# XIAO_ESP32C3.net
KiCad netlist of a schematic drawn in EAGLE
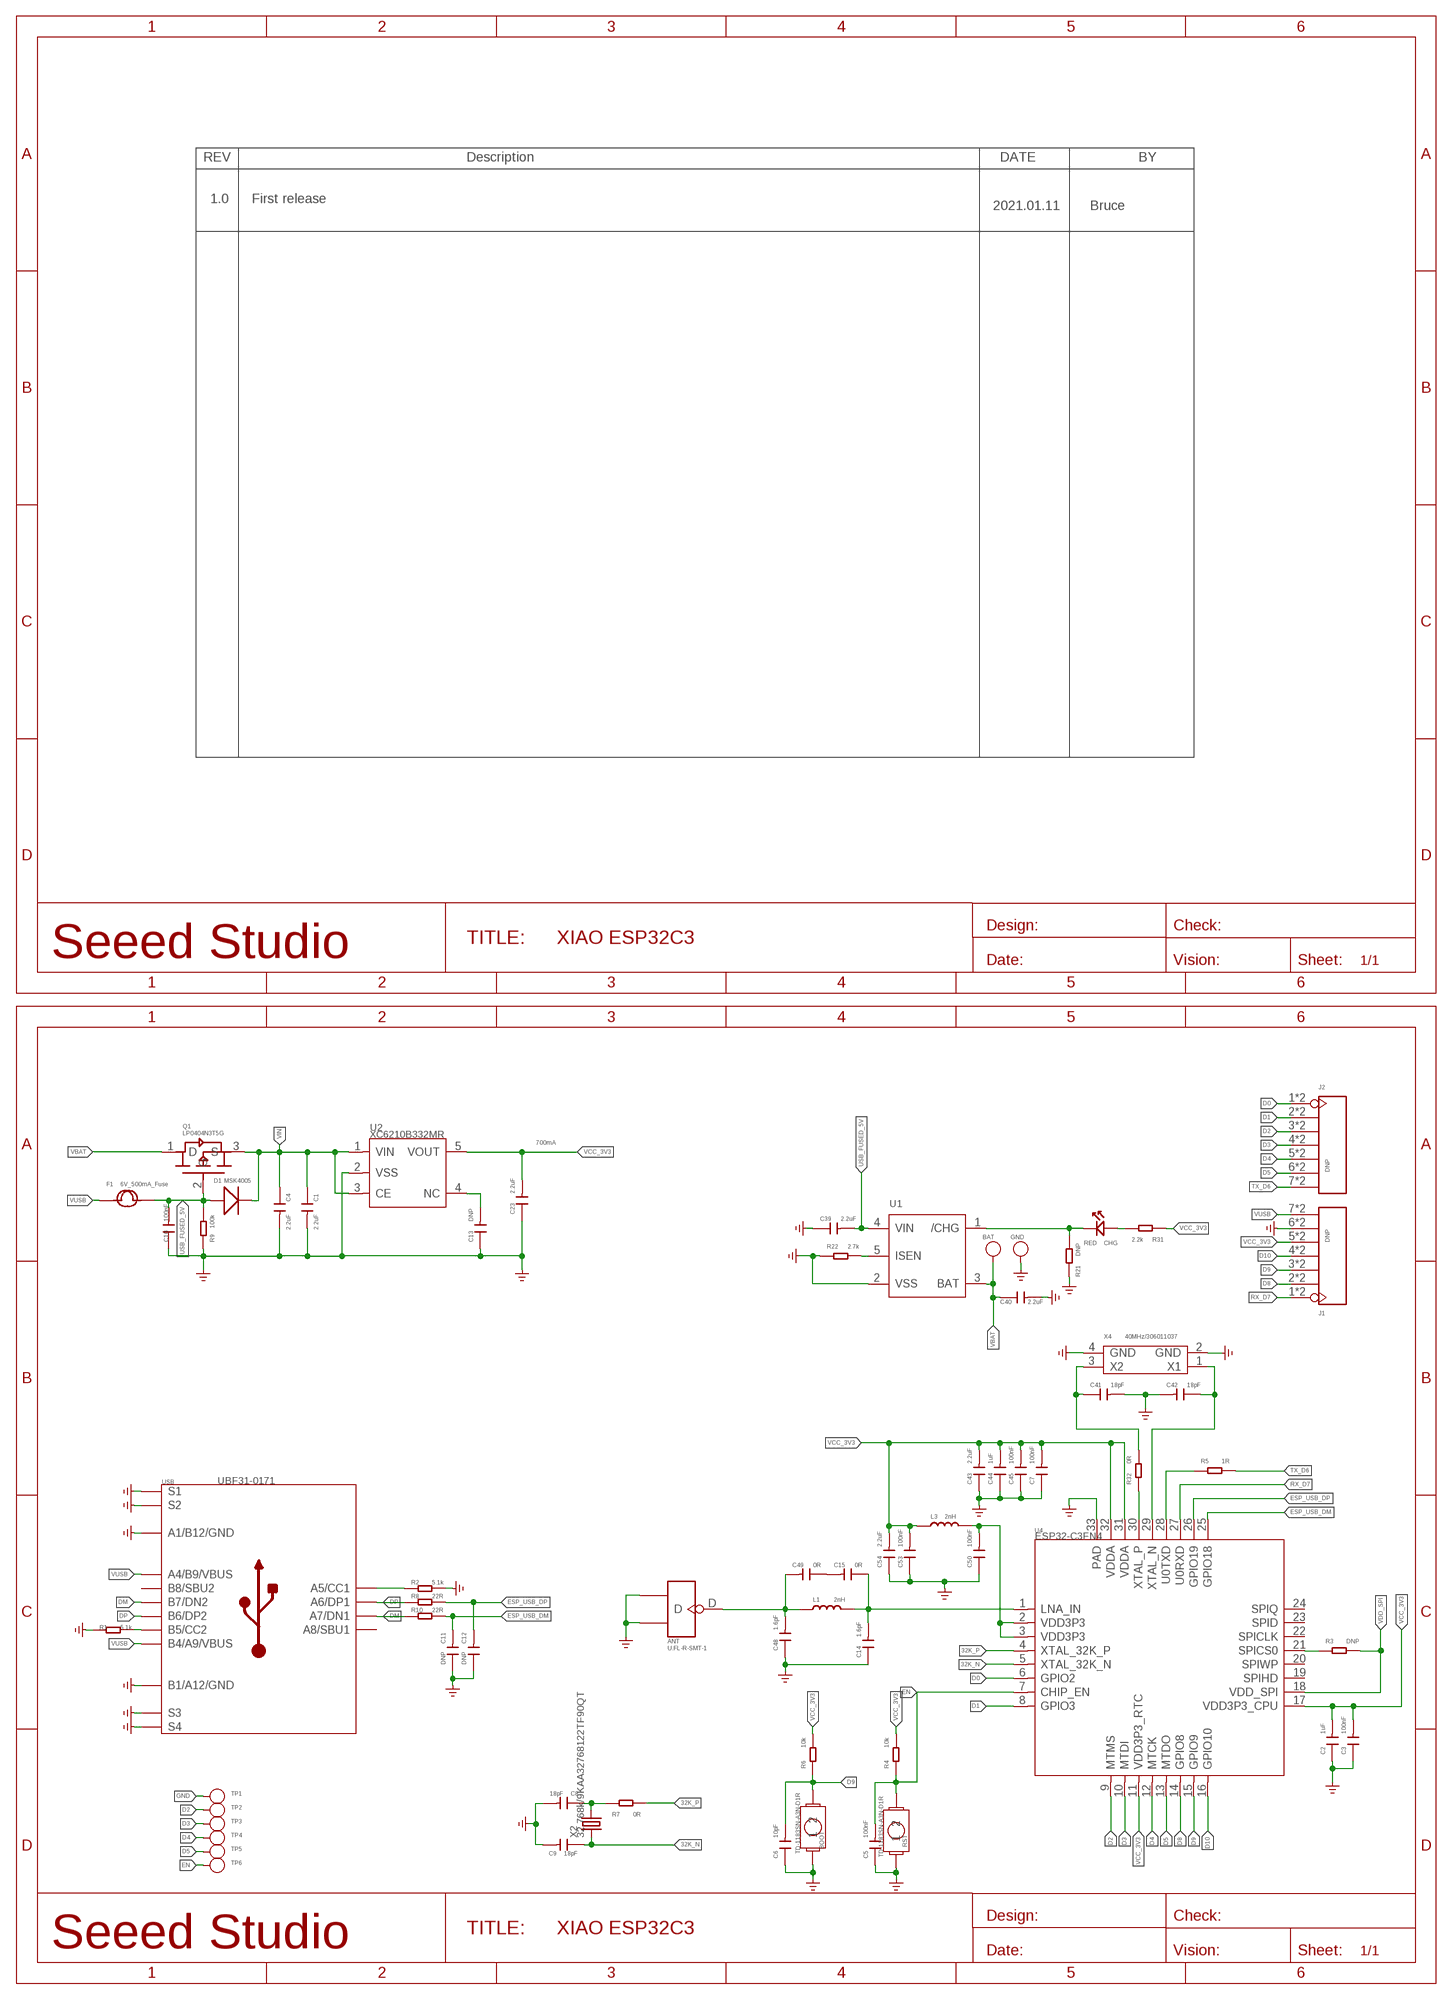
[diagram p0: schematic, sheet 1]

(export (version "E")
  (design (tool "Eeschema 10.0.6"))
  (components
    (comp (ref "ANT")
      (value "U.FL-R-SMT-1")
      (footprint "eagle-import:U-FL3P-SMD-2.6X2.6X1.0MM")
      (libsource (lib "eagle-import") (part "ANTENNA-U-FL-320110048"))
    )
    (comp (ref "BAT")
      (value "DNP")
      (footprint "eagle-import:TP-80X40MIL")
      (libsource (lib "eagle-import") (part "TEST-POINT'4080'"))
    )
    (comp (ref "BOOT")
      (value "TD-1183SN-A3N-D1R")
      (footprint "eagle-import:BUTTON_TD1183SA")
      (libsource (lib "eagle-import") (part "BUTTON_TD1183SA"))
    )
    (comp (ref "C1")
      (value "2.2uF")
      (footprint "eagle-import:C0201")
      (libsource (lib "eagle-import") (part "CAP-0201"))
    )
    (comp (ref "C2")
      (value "1uF")
      (footprint "eagle-import:C0201")
      (libsource (lib "eagle-import") (part "CAP-0201"))
    )
    (comp (ref "C3")
      (value "100nF")
      (footprint "eagle-import:C0201")
      (libsource (lib "eagle-import") (part "CAP-0201"))
    )
    (comp (ref "C4")
      (value "2.2uF")
      (footprint "eagle-import:C0201")
      (libsource (lib "eagle-import") (part "CAP-0201"))
    )
    (comp (ref "C5")
      (value "100nF")
      (footprint "eagle-import:C0201")
      (libsource (lib "eagle-import") (part "CAP-0201"))
    )
    (comp (ref "C6")
      (value "10pF")
      (footprint "eagle-import:C0201")
      (libsource (lib "eagle-import") (part "CAP-0201"))
    )
    (comp (ref "C7")
      (value "100nF")
      (footprint "eagle-import:C0201")
      (libsource (lib "eagle-import") (part "CAP-0201"))
    )
    (comp (ref "C8")
      (value "18pF")
      (footprint "eagle-import:C0201")
      (libsource (lib "eagle-import") (part "CAP-0201"))
    )
    (comp (ref "C9")
      (value "18pF")
      (footprint "eagle-import:C0201")
      (libsource (lib "eagle-import") (part "CAP-0201"))
    )
    (comp (ref "C10")
      (value "100nF")
      (footprint "eagle-import:C0201")
      (libsource (lib "eagle-import") (part "CAP-0201"))
    )
    (comp (ref "C11")
      (value "DNP")
      (footprint "eagle-import:C0201")
      (libsource (lib "eagle-import") (part "CAP-0201"))
    )
    (comp (ref "C12")
      (value "DNP")
      (footprint "eagle-import:C0201")
      (libsource (lib "eagle-import") (part "CAP-0201"))
    )
    (comp (ref "C13")
      (value "DNP")
      (footprint "eagle-import:C0201")
      (libsource (lib "eagle-import") (part "CAP-0201"))
    )
    (comp (ref "C14")
      (value "1.6pF")
      (footprint "eagle-import:C0201")
      (libsource (lib "eagle-import") (part "CAP-0201"))
    )
    (comp (ref "C15")
      (value "0R")
      (footprint "eagle-import:C0201")
      (libsource (lib "eagle-import") (part "CAP-0201"))
    )
    (comp (ref "C23")
      (value "2.2uF")
      (footprint "eagle-import:C0201")
      (libsource (lib "eagle-import") (part "CAP-0201"))
    )
    (comp (ref "C39")
      (value "2.2uF")
      (footprint "eagle-import:C0201")
      (libsource (lib "eagle-import") (part "CAP-0201"))
    )
    (comp (ref "C40")
      (value "2.2uF")
      (footprint "eagle-import:C0201")
      (libsource (lib "eagle-import") (part "CAP-0201"))
    )
    (comp (ref "C41")
      (value "18pF")
      (footprint "eagle-import:C0201")
      (libsource (lib "eagle-import") (part "CAP-0201"))
    )
    (comp (ref "C42")
      (value "18pF")
      (footprint "eagle-import:C0201")
      (libsource (lib "eagle-import") (part "CAP-0201"))
    )
    (comp (ref "C43")
      (value "2.2uF")
      (footprint "eagle-import:C0201")
      (libsource (lib "eagle-import") (part "CAP-0201"))
    )
    (comp (ref "C44")
      (value "1uF")
      (footprint "eagle-import:C0201")
      (libsource (lib "eagle-import") (part "CAP-0201"))
    )
    (comp (ref "C45")
      (value "100nF")
      (footprint "eagle-import:C0201")
      (libsource (lib "eagle-import") (part "CAP-0201"))
    )
    (comp (ref "C48")
      (value "1.6pF")
      (footprint "eagle-import:C0201")
      (libsource (lib "eagle-import") (part "CAP-0201"))
    )
    (comp (ref "C49")
      (value "0R")
      (footprint "eagle-import:C0201")
      (libsource (lib "eagle-import") (part "CAP-0201"))
    )
    (comp (ref "C50")
      (value "100nF")
      (footprint "eagle-import:C0201")
      (libsource (lib "eagle-import") (part "CAP-0201"))
    )
    (comp (ref "C53")
      (value "100nF")
      (footprint "eagle-import:C0201")
      (libsource (lib "eagle-import") (part "CAP-0201"))
    )
    (comp (ref "C54")
      (value "2.2uF")
      (footprint "eagle-import:C0201")
      (libsource (lib "eagle-import") (part "CAP-0201"))
    )
    (comp (ref "CHG")
      (value "RED")
      (footprint "eagle-import:LED-0402")
      (libsource (lib "eagle-import") (part "LED-0402"))
    )
    (comp (ref "D1")
      (value "MSK4005")
      (footprint "eagle-import:SOD-523")
      (libsource (lib "eagle-import") (part "DIODE'0603'"))
    )
    (comp (ref "F1")
      (value "6V_500mA_Fuse")
      (footprint "eagle-import:F0603")
      (libsource (lib "eagle-import") (part "FUSE0603"))
    )
    (comp (ref "GND")
      (value "DNP")
      (footprint "eagle-import:TP-80X40MIL")
      (libsource (lib "eagle-import") (part "TEST-POINT'4080'"))
    )
    (comp (ref "J1")
      (value "DNP")
      (footprint "eagle-import:H7-HALF-HOLE-2.54")
      (libsource (lib "eagle-import") (part "HEADER-7P-HALF-HOLE-2.54"))
    )
    (comp (ref "J2")
      (value "DNP")
      (footprint "eagle-import:H7-HALF-HOLE-2.54")
      (libsource (lib "eagle-import") (part "HEADER-7P-HALF-HOLE-2.54"))
    )
    (comp (ref "L1")
      (value "2nH")
      (footprint "eagle-import:L0201")
      (libsource (lib "eagle-import") (part "INDUCTOR-0201"))
    )
    (comp (ref "L3")
      (value "2nH")
      (footprint "eagle-import:L0201")
      (libsource (lib "eagle-import") (part "INDUCTOR-0201"))
    )
    (comp (ref "Q1")
      (value "LP0404N3T5G")
      (footprint "eagle-import:PMOS_1.0_0.6_0.35MM")
      (libsource (lib "eagle-import") (part "PMOS_1.00.60.35MM"))
    )
    (comp (ref "R1")
      (value "5.1k")
      (footprint "eagle-import:R0201")
      (libsource (lib "eagle-import") (part "RES-0201"))
    )
    (comp (ref "R2")
      (value "5.1k")
      (footprint "eagle-import:R0201")
      (libsource (lib "eagle-import") (part "RES-0201"))
    )
    (comp (ref "R3")
      (value "DNP")
      (footprint "eagle-import:R0201")
      (libsource (lib "eagle-import") (part "RES-0201"))
    )
    (comp (ref "R4")
      (value "10k")
      (footprint "eagle-import:R0201")
      (libsource (lib "eagle-import") (part "RES-0201"))
    )
    (comp (ref "R5")
      (value "1R")
      (footprint "eagle-import:R0201")
      (libsource (lib "eagle-import") (part "RES-0201"))
    )
    (comp (ref "R6")
      (value "10k")
      (footprint "eagle-import:R0201")
      (libsource (lib "eagle-import") (part "RES-0201"))
    )
    (comp (ref "R7")
      (value "0R")
      (footprint "eagle-import:R0201")
      (libsource (lib "eagle-import") (part "RES-0201"))
    )
    (comp (ref "R8")
      (value "22R")
      (footprint "eagle-import:R0201")
      (libsource (lib "eagle-import") (part "RES-0201"))
    )
    (comp (ref "R9")
      (value "100k")
      (footprint "eagle-import:R0201")
      (libsource (lib "eagle-import") (part "RES-0201"))
    )
    (comp (ref "R10")
      (value "22R")
      (footprint "eagle-import:R0201")
      (libsource (lib "eagle-import") (part "RES-0201"))
    )
    (comp (ref "R21")
      (value "DNP")
      (footprint "eagle-import:R0201")
      (libsource (lib "eagle-import") (part "R-0201"))
    )
    (comp (ref "R22")
      (value "2.7k")
      (footprint "eagle-import:R0201")
      (libsource (lib "eagle-import") (part "RES-0201"))
    )
    (comp (ref "R31")
      (value "2.2k")
      (footprint "eagle-import:R0201")
      (libsource (lib "eagle-import") (part "RES-0201"))
    )
    (comp (ref "R32")
      (value "0R")
      (footprint "eagle-import:R0201")
      (libsource (lib "eagle-import") (part "RES-0201"))
    )
    (comp (ref "RST")
      (value "TD-1183SN-A3N-D1R")
      (footprint "eagle-import:BUTTON_TD1183SA")
      (libsource (lib "eagle-import") (part "BUTTON_TD1183SA"))
    )
    (comp (ref "TP1")
      (value "DNP")
      (footprint "eagle-import:TP-D45MIL")
      (libsource (lib "eagle-import") (part "TEST-POINT'4545'"))
    )
    (comp (ref "TP2")
      (value "DNP")
      (footprint "eagle-import:TP-D45MIL")
      (libsource (lib "eagle-import") (part "TEST-POINT'4545'"))
    )
    (comp (ref "TP3")
      (value "DNP")
      (footprint "eagle-import:TP-D45MIL")
      (libsource (lib "eagle-import") (part "TEST-POINT'4545'"))
    )
    (comp (ref "TP4")
      (value "DNP")
      (footprint "eagle-import:TP-D45MIL")
      (libsource (lib "eagle-import") (part "TEST-POINT'4545'"))
    )
    (comp (ref "TP5")
      (value "DNP")
      (footprint "eagle-import:TP-D45MIL")
      (libsource (lib "eagle-import") (part "TEST-POINT'4545'"))
    )
    (comp (ref "TP6")
      (value "DNP")
      (footprint "eagle-import:TP-D45MIL")
      (libsource (lib "eagle-import") (part "TEST-POINT'4545'"))
    )
    (comp (ref "U1")
      (value "PMIC-XC6802MR")
      (footprint "eagle-import:SOT-25")
      (libsource (lib "eagle-import") (part "PMIC-XC6802MR"))
    )
    (comp (ref "U2")
      (value "XC6210B332MR")
      (footprint "eagle-import:SOT-25")
      (libsource (lib "eagle-import") (part "PMIC-LDO-XC6210-5P"))
    )
    (comp (ref "U4")
      (value "ESP32-C3FN4")
      (footprint "eagle-import:QFN32G-0.5-5X5MM")
      (libsource (lib "eagle-import") (part "MCU-ESP32-C3"))
    )
    (comp (ref "USB")
      (value "UBF31-0171")
      (footprint "eagle-import:USB2.0-TYPE-C")
      (libsource (lib "eagle-import") (part "USB2.0-TYPE-C"))
    )
    (comp (ref "X2")
      (value "32.768k/9KAA32768122TF90QT")
      (footprint "eagle-import:X2-SMD-1.6X1.0X0.5MM")
      (libsource (lib "eagle-import") (part "CRYSTAL-2P-1610"))
    )
    (comp (ref "X4")
      (value "40MHz/306011037")
      (footprint "eagle-import:X4-SMD-2.0X1.6X0.5MM")
      (libsource (lib "eagle-import") (part "CRYSTAL-4P-2016"))
    )
  )
  (nets
    (net (code "1") (name "32K_N") (class "Default")
      (node (ref "C9") (pin "1") (pinfunction "1_1") (pintype "passive"))
      (node (ref "U4") (pin "5") (pinfunction "XTAL_32K_N_5") (pintype "bidirectional"))
      (node (ref "X2") (pin "1") (pinfunction "1_1") (pintype "passive"))
    )
    (net (code "2") (name "32K_P") (class "Default")
      (node (ref "R7") (pin "1") (pinfunction "1_1") (pintype "passive"))
      (node (ref "U4") (pin "4") (pinfunction "XTAL_32K_P_4") (pintype "bidirectional"))
    )
    (net (code "3") (name "D0") (class "Default")
      (node (ref "J2") (pin "1") (pinfunction "1_1") (pintype "bidirectional"))
      (node (ref "J2") (pin "13") (pinfunction "1_13") (pintype "bidirectional"))
      (node (ref "U4") (pin "6") (pinfunction "GPIO2_6") (pintype "bidirectional"))
    )
    (net (code "4") (name "D1") (class "Default")
      (node (ref "J2") (pin "14") (pinfunction "2_14") (pintype "bidirectional"))
      (node (ref "J2") (pin "2") (pinfunction "2_2") (pintype "bidirectional"))
      (node (ref "U4") (pin "8") (pinfunction "GPIO3_8") (pintype "bidirectional"))
    )
    (net (code "5") (name "D2") (class "Default")
      (node (ref "J2") (pin "15") (pinfunction "3_15") (pintype "bidirectional"))
      (node (ref "J2") (pin "3") (pinfunction "3_3") (pintype "bidirectional"))
      (node (ref "TP2") (pin "T") (pinfunction "T_T") (pintype "bidirectional"))
      (node (ref "U4") (pin "9") (pinfunction "MTMS_9") (pintype "bidirectional"))
    )
    (net (code "6") (name "D3") (class "Default")
      (node (ref "J2") (pin "16") (pinfunction "4_16") (pintype "bidirectional"))
      (node (ref "J2") (pin "4") (pinfunction "4_4") (pintype "bidirectional"))
      (node (ref "TP3") (pin "T") (pinfunction "T_T") (pintype "bidirectional"))
      (node (ref "U4") (pin "10") (pinfunction "MTDI_10") (pintype "bidirectional"))
    )
    (net (code "7") (name "D4") (class "Default")
      (node (ref "J2") (pin "17") (pinfunction "5_17") (pintype "bidirectional"))
      (node (ref "J2") (pin "5") (pinfunction "5_5") (pintype "bidirectional"))
      (node (ref "TP4") (pin "T") (pinfunction "T_T") (pintype "bidirectional"))
      (node (ref "U4") (pin "12") (pinfunction "MTCK_12") (pintype "bidirectional"))
    )
    (net (code "8") (name "D5") (class "Default")
      (node (ref "J2") (pin "18") (pinfunction "6_18") (pintype "bidirectional"))
      (node (ref "J2") (pin "6") (pinfunction "6_6") (pintype "bidirectional"))
      (node (ref "TP5") (pin "T") (pinfunction "T_T") (pintype "bidirectional"))
      (node (ref "U4") (pin "13") (pinfunction "MTDO_13") (pintype "bidirectional"))
    )
    (net (code "9") (name "D8") (class "Default")
      (node (ref "J1") (pin "14") (pinfunction "2_14") (pintype "bidirectional"))
      (node (ref "J1") (pin "2") (pinfunction "2_2") (pintype "bidirectional"))
      (node (ref "U4") (pin "14") (pinfunction "GPIO8_14") (pintype "bidirectional"))
    )
    (net (code "10") (name "D9") (class "Default")
      (node (ref "BOOT") (pin "2") (pinfunction "2_2") (pintype "bidirectional"))
      (node (ref "C6") (pin "2") (pinfunction "2_2") (pintype "passive"))
      (node (ref "J1") (pin "15") (pinfunction "3_15") (pintype "bidirectional"))
      (node (ref "J1") (pin "3") (pinfunction "3_3") (pintype "bidirectional"))
      (node (ref "R6") (pin "1") (pinfunction "1_1") (pintype "passive"))
      (node (ref "U4") (pin "15") (pinfunction "GPIO9_15") (pintype "bidirectional"))
    )
    (net (code "11") (name "D10") (class "Default")
      (node (ref "J1") (pin "16") (pinfunction "4_16") (pintype "bidirectional"))
      (node (ref "J1") (pin "4") (pinfunction "4_4") (pintype "bidirectional"))
      (node (ref "U4") (pin "16") (pinfunction "GPIO10_16") (pintype "bidirectional"))
    )
    (net (code "12") (name "DM") (class "Default")
      (node (ref "R10") (pin "1") (pinfunction "1_1") (pintype "passive"))
      (node (ref "USB") (pin "A7") (pinfunction "A7/DN1_A7") (pintype "bidirectional"))
      (node (ref "USB") (pin "B7") (pinfunction "B7/DN2_B7") (pintype "bidirectional"))
    )
    (net (code "13") (name "DP") (class "Default")
      (node (ref "R8") (pin "1") (pinfunction "1_1") (pintype "passive"))
      (node (ref "USB") (pin "A6") (pinfunction "A6/DP1_A6") (pintype "bidirectional"))
      (node (ref "USB") (pin "B6") (pinfunction "B6/DP2_B6") (pintype "bidirectional"))
    )
    (net (code "14") (name "EN") (class "Default")
      (node (ref "C5") (pin "2") (pinfunction "2_2") (pintype "passive"))
      (node (ref "R4") (pin "1") (pinfunction "1_1") (pintype "passive"))
      (node (ref "RST") (pin "2") (pinfunction "2_2") (pintype "bidirectional"))
      (node (ref "TP6") (pin "T") (pinfunction "T_T") (pintype "bidirectional"))
      (node (ref "U4") (pin "7") (pinfunction "CHIP_EN_7") (pintype "bidirectional"))
    )
    (net (code "15") (name "ESP_USB_DM") (class "Default")
      (node (ref "C11") (pin "2") (pinfunction "2_2") (pintype "passive"))
      (node (ref "R10") (pin "2") (pinfunction "2_2") (pintype "passive"))
      (node (ref "U4") (pin "25") (pinfunction "GPIO18_25") (pintype "bidirectional"))
    )
    (net (code "16") (name "ESP_USB_DP") (class "Default")
      (node (ref "C12") (pin "2") (pinfunction "2_2") (pintype "passive"))
      (node (ref "R8") (pin "2") (pinfunction "2_2") (pintype "passive"))
      (node (ref "U4") (pin "26") (pinfunction "GPIO19_26") (pintype "bidirectional"))
    )
    (net (code "17") (name "GND") (class "Default")
      (node (ref "ANT") (pin "GND1") (pinfunction "GND1_GND1") (pintype "bidirectional"))
      (node (ref "ANT") (pin "GND2") (pinfunction "GND2_GND2") (pintype "bidirectional"))
      (node (ref "BOOT") (pin "1") (pinfunction "1_1") (pintype "bidirectional"))
      (node (ref "C1") (pin "2") (pinfunction "2_2") (pintype "passive"))
      (node (ref "C10") (pin "1") (pinfunction "1_1") (pintype "passive"))
      (node (ref "C11") (pin "1") (pinfunction "1_1") (pintype "passive"))
      (node (ref "C12") (pin "1") (pinfunction "1_1") (pintype "passive"))
      (node (ref "C13") (pin "1") (pinfunction "1_1") (pintype "passive"))
      (node (ref "C14") (pin "1") (pinfunction "1_1") (pintype "passive"))
      (node (ref "C2") (pin "1") (pinfunction "1_1") (pintype "passive"))
      (node (ref "C23") (pin "1") (pinfunction "1_1") (pintype "passive"))
      (node (ref "C3") (pin "1") (pinfunction "1_1") (pintype "passive"))
      (node (ref "C39") (pin "1") (pinfunction "1_1") (pintype "passive"))
      (node (ref "C4") (pin "2") (pinfunction "2_2") (pintype "passive"))
      (node (ref "C40") (pin "2") (pinfunction "2_2") (pintype "passive"))
      (node (ref "C41") (pin "2") (pinfunction "2_2") (pintype "passive"))
      (node (ref "C42") (pin "2") (pinfunction "2_2") (pintype "passive"))
      (node (ref "C43") (pin "1") (pinfunction "1_1") (pintype "passive"))
      (node (ref "C44") (pin "1") (pinfunction "1_1") (pintype "passive"))
      (node (ref "C45") (pin "1") (pinfunction "1_1") (pintype "passive"))
      (node (ref "C48") (pin "1") (pinfunction "1_1") (pintype "passive"))
      (node (ref "C5") (pin "1") (pinfunction "1_1") (pintype "passive"))
      (node (ref "C50") (pin "1") (pinfunction "1_1") (pintype "passive"))
      (node (ref "C53") (pin "1") (pinfunction "1_1") (pintype "passive"))
      (node (ref "C54") (pin "1") (pinfunction "1_1") (pintype "passive"))
      (node (ref "C6") (pin "1") (pinfunction "1_1") (pintype "passive"))
      (node (ref "C7") (pin "1") (pinfunction "1_1") (pintype "passive"))
      (node (ref "C8") (pin "2") (pinfunction "2_2") (pintype "passive"))
      (node (ref "C9") (pin "2") (pinfunction "2_2") (pintype "passive"))
      (node (ref "GND") (pin "1") (pinfunction "T_1") (pintype "bidirectional"))
      (node (ref "J1") (pin "18") (pinfunction "6_18") (pintype "bidirectional"))
      (node (ref "J1") (pin "6") (pinfunction "6_6") (pintype "bidirectional"))
      (node (ref "R1") (pin "1") (pinfunction "1_1") (pintype "passive"))
      (node (ref "R2") (pin "2") (pinfunction "2_2") (pintype "passive"))
      (node (ref "R21") (pin "2") (pinfunction "2_2") (pintype "passive"))
      (node (ref "R22") (pin "2") (pinfunction "2_2") (pintype "passive"))
      (node (ref "R9") (pin "1") (pinfunction "1_1") (pintype "passive"))
      (node (ref "RST") (pin "1") (pinfunction "1_1") (pintype "bidirectional"))
      (node (ref "TP1") (pin "T") (pinfunction "T_T") (pintype "bidirectional"))
      (node (ref "U1") (pin "2") (pinfunction "VSS_2") (pintype "bidirectional"))
      (node (ref "U2") (pin "2") (pinfunction "VSS_2") (pintype "bidirectional"))
      (node (ref "U4") (pin "33") (pinfunction "PAD_33") (pintype "bidirectional"))
      (node (ref "USB") (pin "A1_B12") (pinfunction "A1/B12/GND_A1_B12") (pintype "bidirectional"))
      (node (ref "USB") (pin "B1_A12") (pinfunction "B1/A12/GND_B1_A12") (pintype "bidirectional"))
      (node (ref "USB") (pin "S1") (pinfunction "S1_S1") (pintype "bidirectional"))
      (node (ref "USB") (pin "S2") (pinfunction "S2_S2") (pintype "bidirectional"))
      (node (ref "USB") (pin "S3") (pinfunction "S3_S3") (pintype "bidirectional"))
      (node (ref "USB") (pin "S4") (pinfunction "S4_S4") (pintype "bidirectional"))
      (node (ref "USB") (pin "S5") (pinfunction "S1_S5") (pintype "bidirectional"))
      (node (ref "USB") (pin "S6") (pinfunction "S2_S6") (pintype "bidirectional"))
      (node (ref "X4") (pin "2") (pinfunction "GND_2") (pintype "bidirectional"))
      (node (ref "X4") (pin "4") (pinfunction "GND_4") (pintype "bidirectional"))
    )
    (net (code "18") (name "Net-(ANT-PadD)") (class "Default")
      (node (ref "ANT") (pin "D") (pinfunction "D_D") (pintype "bidirectional"))
      (node (ref "C48") (pin "2") (pinfunction "2_2") (pintype "passive"))
      (node (ref "C49") (pin "2") (pinfunction "2_2") (pintype "passive"))
      (node (ref "L1") (pin "1") (pinfunction "1_1") (pintype "passive"))
    )
    (net (code "19") (name "Net-(C8-Pad1)") (class "Default")
      (node (ref "C8") (pin "1") (pinfunction "1_1") (pintype "passive"))
      (node (ref "R7") (pin "2") (pinfunction "2_2") (pintype "passive"))
      (node (ref "X2") (pin "2") (pinfunction "2_2") (pintype "passive"))
    )
    (net (code "20") (name "Net-(C15-Pad2)") (class "Default")
      (node (ref "C15") (pin "2") (pinfunction "2_2") (pintype "passive"))
      (node (ref "C49") (pin "1") (pinfunction "1_1") (pintype "passive"))
    )
    (net (code "21") (name "Net-(C50-Pad2)") (class "Default")
      (node (ref "C50") (pin "2") (pinfunction "2_2") (pintype "passive"))
      (node (ref "L3") (pin "2") (pinfunction "2_2") (pintype "passive"))
      (node (ref "U4") (pin "2") (pinfunction "VDD3P3_2") (pintype "bidirectional"))
      (node (ref "U4") (pin "3") (pinfunction "VDD3P3_3") (pintype "bidirectional"))
    )
    (net (code "22") (name "Net-(CHG-Pad+)") (class "Default")
      (node (ref "CHG") (pin "+") (pinfunction "+_+") (pintype "passive"))
      (node (ref "R31") (pin "2") (pinfunction "2_2") (pintype "passive"))
    )
    (net (code "23") (name "Net-(U1-ISEN)") (class "Default")
      (node (ref "R22") (pin "1") (pinfunction "1_1") (pintype "passive"))
      (node (ref "U1") (pin "5") (pinfunction "ISEN_5") (pintype "bidirectional"))
    )
    (net (code "24") (name "Net-(U1-{slash}CHG)") (class "Default")
      (node (ref "CHG") (pin "-") (pinfunction "-_-") (pintype "passive"))
      (node (ref "R21") (pin "1") (pinfunction "1_1") (pintype "passive"))
      (node (ref "U1") (pin "1") (pinfunction "/CHG_1") (pintype "bidirectional"))
    )
    (net (code "25") (name "Net-(U2-NC)") (class "Default")
      (node (ref "C13") (pin "2") (pinfunction "2_2") (pintype "passive"))
      (node (ref "U2") (pin "4") (pinfunction "NC_4") (pintype "bidirectional"))
    )
    (net (code "26") (name "Net-(U4-LNA_IN)") (class "Default")
      (node (ref "C14") (pin "2") (pinfunction "2_2") (pintype "passive"))
      (node (ref "C15") (pin "1") (pinfunction "1_1") (pintype "passive"))
      (node (ref "L1") (pin "2") (pinfunction "2_2") (pintype "passive"))
      (node (ref "U4") (pin "1") (pinfunction "LNA_IN_1") (pintype "bidirectional"))
    )
    (net (code "27") (name "Net-(U4-SPICS0)") (class "Default")
      (node (ref "R3") (pin "1") (pinfunction "1_1") (pintype "passive"))
      (node (ref "U4") (pin "21") (pinfunction "SPICS0_21") (pintype "bidirectional"))
    )
    (net (code "28") (name "Net-(U4-U0TXD)") (class "Default")
      (node (ref "R5") (pin "2") (pinfunction "2_2") (pintype "passive"))
      (node (ref "U4") (pin "28") (pinfunction "U0TXD_28") (pintype "bidirectional"))
    )
    (net (code "29") (name "Net-(U4-XTAL_N)") (class "Default")
      (node (ref "C42") (pin "1") (pinfunction "1_1") (pintype "passive"))
      (node (ref "U4") (pin "29") (pinfunction "XTAL_N_29") (pintype "bidirectional"))
      (node (ref "X4") (pin "1") (pinfunction "X1_1") (pintype "bidirectional"))
    )
    (net (code "30") (name "Net-(U4-XTAL_P)") (class "Default")
      (node (ref "R32") (pin "1") (pinfunction "1_1") (pintype "passive"))
      (node (ref "U4") (pin "30") (pinfunction "XTAL_P_30") (pintype "bidirectional"))
    )
    (net (code "31") (name "Net-(USB-A5{slash}CC1)") (class "Default")
      (node (ref "R2") (pin "1") (pinfunction "1_1") (pintype "passive"))
      (node (ref "USB") (pin "A5") (pinfunction "A5/CC1_A5") (pintype "bidirectional"))
    )
    (net (code "32") (name "Net-(USB-B5{slash}CC2)") (class "Default")
      (node (ref "R1") (pin "2") (pinfunction "2_2") (pintype "passive"))
      (node (ref "USB") (pin "B5") (pinfunction "B5/CC2_B5") (pintype "bidirectional"))
    )
    (net (code "33") (name "Net-(X4-X2)") (class "Default")
      (node (ref "C41") (pin "1") (pinfunction "1_1") (pintype "passive"))
      (node (ref "R32") (pin "2") (pinfunction "2_2") (pintype "passive"))
      (node (ref "X4") (pin "3") (pinfunction "X2_3") (pintype "bidirectional"))
    )
    (net (code "34") (name "RX_D7") (class "Default")
      (node (ref "J1") (pin "1") (pinfunction "1_1") (pintype "bidirectional"))
      (node (ref "J1") (pin "13") (pinfunction "1_13") (pintype "bidirectional"))
      (node (ref "U4") (pin "27") (pinfunction "U0RXD_27") (pintype "bidirectional"))
    )
    (net (code "35") (name "TX_D6") (class "Default")
      (node (ref "J2") (pin "19") (pinfunction "7_19") (pintype "bidirectional"))
      (node (ref "J2") (pin "7") (pinfunction "7_7") (pintype "bidirectional"))
      (node (ref "R5") (pin "1") (pinfunction "1_1") (pintype "passive"))
    )
    (net (code "36") (name "USB_FUSED_5V") (class "Default")
      (node (ref "C10") (pin "2") (pinfunction "2_2") (pintype "passive"))
      (node (ref "C39") (pin "2") (pinfunction "2_2") (pintype "passive"))
      (node (ref "D1") (pin "+") (pinfunction "+_+") (pintype "passive"))
      (node (ref "F1") (pin "2") (pinfunction "2_2") (pintype "bidirectional"))
      (node (ref "Q1") (pin "2") (pinfunction "G_2") (pintype "bidirectional"))
      (node (ref "R9") (pin "2") (pinfunction "2_2") (pintype "passive"))
      (node (ref "U1") (pin "4") (pinfunction "VIN_4") (pintype "bidirectional"))
    )
    (net (code "37") (name "VBAT") (class "Default")
      (node (ref "BAT") (pin "1") (pinfunction "T_1") (pintype "bidirectional"))
      (node (ref "C40") (pin "1") (pinfunction "1_1") (pintype "passive"))
      (node (ref "Q1") (pin "1") (pinfunction "D_1") (pintype "bidirectional"))
      (node (ref "U1") (pin "3") (pinfunction "BAT_3") (pintype "bidirectional"))
    )
    (net (code "38") (name "VCC_3V3") (class "Default")
      (node (ref "C2") (pin "2") (pinfunction "2_2") (pintype "passive"))
      (node (ref "C23") (pin "2") (pinfunction "2_2") (pintype "passive"))
      (node (ref "C3") (pin "2") (pinfunction "2_2") (pintype "passive"))
      (node (ref "C43") (pin "2") (pinfunction "2_2") (pintype "passive"))
      (node (ref "C44") (pin "2") (pinfunction "2_2") (pintype "passive"))
      (node (ref "C45") (pin "2") (pinfunction "2_2") (pintype "passive"))
      (node (ref "C53") (pin "2") (pinfunction "2_2") (pintype "passive"))
      (node (ref "C54") (pin "2") (pinfunction "2_2") (pintype "passive"))
      (node (ref "C7") (pin "2") (pinfunction "2_2") (pintype "passive"))
      (node (ref "J1") (pin "17") (pinfunction "5_17") (pintype "bidirectional"))
      (node (ref "J1") (pin "5") (pinfunction "5_5") (pintype "bidirectional"))
      (node (ref "L3") (pin "1") (pinfunction "1_1") (pintype "passive"))
      (node (ref "R31") (pin "1") (pinfunction "1_1") (pintype "passive"))
      (node (ref "R4") (pin "2") (pinfunction "2_2") (pintype "passive"))
      (node (ref "R6") (pin "2") (pinfunction "2_2") (pintype "passive"))
      (node (ref "U2") (pin "5") (pinfunction "VOUT_5") (pintype "bidirectional"))
      (node (ref "U4") (pin "11") (pinfunction "VDD3P3_RTC_11") (pintype "bidirectional"))
      (node (ref "U4") (pin "17") (pinfunction "VDD3P3_CPU_17") (pintype "bidirectional"))
      (node (ref "U4") (pin "31") (pinfunction "VDDA_31") (pintype "bidirectional"))
      (node (ref "U4") (pin "32") (pinfunction "VDDA_32") (pintype "bidirectional"))
    )
    (net (code "39") (name "VDD_SPI") (class "Default")
      (node (ref "R3") (pin "2") (pinfunction "2_2") (pintype "passive"))
      (node (ref "U4") (pin "18") (pinfunction "VDD_SPI_18") (pintype "bidirectional"))
    )
    (net (code "40") (name "VIN") (class "Default")
      (node (ref "C1") (pin "1") (pinfunction "1_1") (pintype "passive"))
      (node (ref "C4") (pin "1") (pinfunction "1_1") (pintype "passive"))
      (node (ref "D1") (pin "-") (pinfunction "-_-") (pintype "passive"))
      (node (ref "Q1") (pin "3") (pinfunction "S_3") (pintype "bidirectional"))
      (node (ref "U2") (pin "1") (pinfunction "VIN_1") (pintype "bidirectional"))
      (node (ref "U2") (pin "3") (pinfunction "CE_3") (pintype "bidirectional"))
    )
    (net (code "41") (name "VUSB") (class "Default")
      (node (ref "F1") (pin "1") (pinfunction "1_1") (pintype "bidirectional"))
      (node (ref "J1") (pin "19") (pinfunction "7_19") (pintype "bidirectional"))
      (node (ref "J1") (pin "7") (pinfunction "7_7") (pintype "bidirectional"))
      (node (ref "USB") (pin "A4_B9") (pinfunction "A4/B9/VBUS_A4_B9") (pintype "bidirectional"))
      (node (ref "USB") (pin "B4_A9") (pinfunction "B4/A9/VBUS_B4_A9") (pintype "bidirectional"))
    )
    (net (code "42") (name "unconnected-(U4-SPICLK-Pad22)") (class "Default")
      (node (ref "U4") (pin "22") (pinfunction "SPICLK_22") (pintype "bidirectional"))
    )
    (net (code "43") (name "unconnected-(U4-SPID-Pad23)") (class "Default")
      (node (ref "U4") (pin "23") (pinfunction "SPID_23") (pintype "bidirectional"))
    )
    (net (code "44") (name "unconnected-(U4-SPIHD-Pad19)") (class "Default")
      (node (ref "U4") (pin "19") (pinfunction "SPIHD_19") (pintype "bidirectional"))
    )
    (net (code "45") (name "unconnected-(U4-SPIQ-Pad24)") (class "Default")
      (node (ref "U4") (pin "24") (pinfunction "SPIQ_24") (pintype "bidirectional"))
    )
    (net (code "46") (name "unconnected-(U4-SPIWP-Pad20)") (class "Default")
      (node (ref "U4") (pin "20") (pinfunction "SPIWP_20") (pintype "bidirectional"))
    )
    (net (code "47") (name "unconnected-(USB-A8{slash}SBU1-PadA8)") (class "Default")
      (node (ref "USB") (pin "A8") (pinfunction "A8/SBU1_A8") (pintype "bidirectional"))
    )
    (net (code "48") (name "unconnected-(USB-B8{slash}SBU2-PadB8)") (class "Default")
      (node (ref "USB") (pin "B8") (pinfunction "B8/SBU2_B8") (pintype "bidirectional"))
    )
  )
)
